# RAC_schematic_pcb.net
KiCad netlist of a schematic drawn in EasyEDA Pro
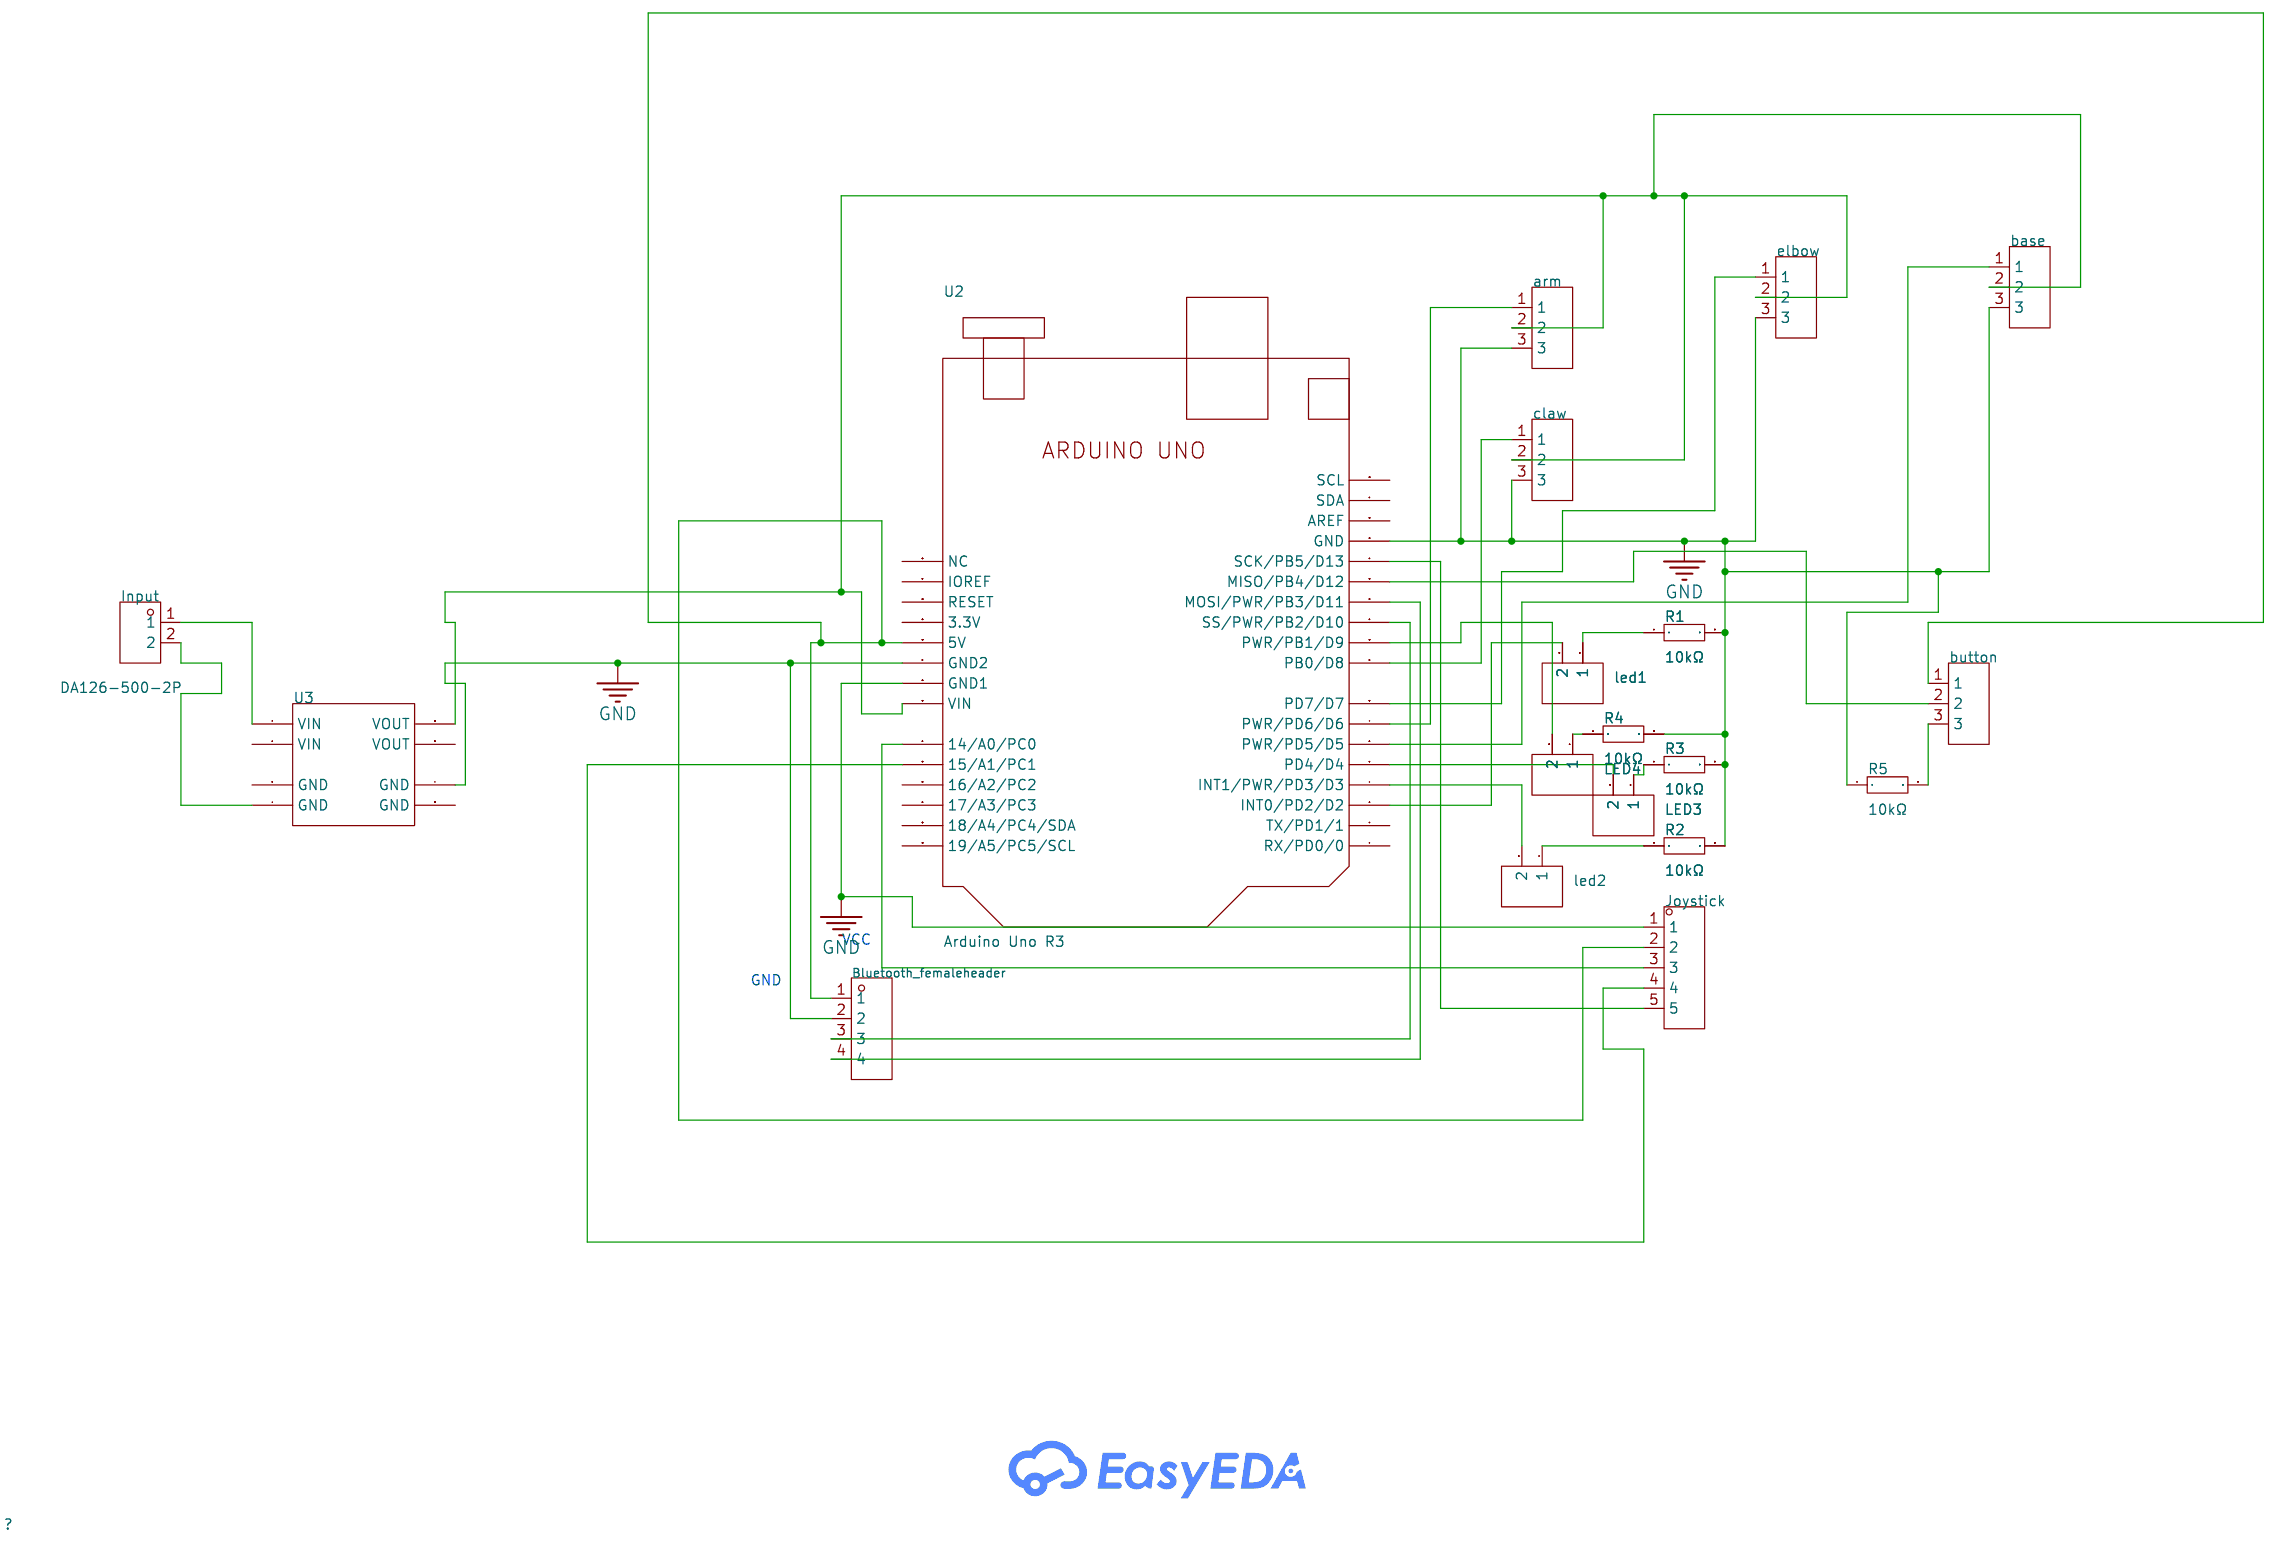
[diagram p0: schematic sheet]

(export (version "E")
  (design (tool "Eeschema 10.0.6"))
  (components
    (comp (ref "arm")
      (value "~")
      (footprint "easyedapro:HDR-TH_3P-P2.54-V-M")
      (libsource (lib "easyedapro") (part "PZ254V-11-03P_C2937625"))
    )
    (comp (ref "base")
      (value "~")
      (footprint "easyedapro:HDR-TH_3P-P2.54-V-M")
      (libsource (lib "easyedapro") (part "PZ254V-11-03P_C2937625"))
    )
    (comp (ref "Bluetooth_femaleheader")
      (value "~")
      (footprint "easyedapro:HDR-TH_4P-P2.54-V-F")
      (libsource (lib "easyedapro") (part "2.54-1*4P母"))
    )
    (comp (ref "button")
      (value "~")
      (footprint "easyedapro:HDR-TH_3P-P2.54-V-M")
      (libsource (lib "easyedapro") (part "PZ254V-11-03P_C2937625"))
    )
    (comp (ref "claw")
      (value "~")
      (footprint "easyedapro:HDR-TH_3P-P2.54-V-M")
      (libsource (lib "easyedapro") (part "PZ254V-11-03P_C2937625"))
    )
    (comp (ref "elbow")
      (value "~")
      (footprint "easyedapro:HDR-TH_3P-P2.54-V-M")
      (libsource (lib "easyedapro") (part "PZ254V-11-03P_C2937625"))
    )
    (comp (ref "Input")
      (value "DA126-500-2P")
      (footprint "easyedapro:CONN-TH_DA126-500-2P")
      (libsource (lib "easyedapro") (part "DA126-500-2P"))
    )
    (comp (ref "Joystick")
      (value "~")
      (footprint "easyedapro:HDR-TH_5P-P2.54-V-M")
      (libsource (lib "easyedapro") (part "MTP125-1105S1"))
    )
    (comp (ref "led1")
      (value "~")
      (footprint "easyedapro:HDR-TH_2P-P2.54-V-F")
      (fields (field (name "Manufacturer Part") "2.54-1*2P母") (field (name "Manufacturer") "BOOMELE(博穆精密)"))
      (libsource (lib "easyedapro") (part "Header-Female-2.54_1x2"))
    )
    (comp (ref "led2")
      (value "~")
      (footprint "easyedapro:HDR-TH_2P-P2.54-V-F")
      (fields (field (name "Manufacturer Part") "2.54-1*2P母") (field (name "Manufacturer") "BOOMELE(博穆精密)"))
      (libsource (lib "easyedapro") (part "Header-Female-2.54_1x2"))
    )
    (comp (ref "LED3")
      (value "~")
      (footprint "easyedapro:HDR-TH_2P-P2.54-V-F")
      (fields (field (name "Manufacturer Part") "2.54-1*2P母") (field (name "Manufacturer") "BOOMELE(博穆精密)"))
      (libsource (lib "easyedapro") (part "Header-Female-2.54_1x2"))
    )
    (comp (ref "LED4")
      (value "~")
      (footprint "easyedapro:HDR-TH_2P-P2.54-V-F")
      (fields (field (name "Manufacturer Part") "2.54-1*2P母") (field (name "Manufacturer") "BOOMELE(博穆精密)"))
      (libsource (lib "easyedapro") (part "Header-Female-2.54_1x2"))
    )
    (comp (ref "R1")
      (value "10kΩ")
      (footprint "easyedapro:R_AXIAL-0.4")
      (libsource (lib "easyedapro") (part "Res"))
    )
    (comp (ref "R2")
      (value "10kΩ")
      (footprint "easyedapro:R_AXIAL-0.4")
      (libsource (lib "easyedapro") (part "Res"))
    )
    (comp (ref "R3")
      (value "10kΩ")
      (footprint "easyedapro:R_AXIAL-0.4")
      (libsource (lib "easyedapro") (part "Res"))
    )
    (comp (ref "R4")
      (value "10kΩ")
      (footprint "easyedapro:R_AXIAL-0.4")
      (libsource (lib "easyedapro") (part "Res"))
    )
    (comp (ref "R5")
      (value "10kΩ")
      (footprint "easyedapro:R_AXIAL-0.4")
      (libsource (lib "easyedapro") (part "Res"))
    )
    (comp (ref "U2")
      (value "Arduino Uno R3")
      (footprint "easyedapro:UNO_R3;WO ARDUINO UNO")
      (fields (field (name "Manufacturer") "Arduino CC"))
      (libsource (lib "easyedapro") (part "Arduino Uno R3"))
    )
    (comp (ref "U3")
      (value "~")
      (footprint "easyedapro:Mini560")
      (libsource (lib "easyedapro") (part "Mini560"))
    )
  )
  (nets
    (net (code "1") (name "GND") (class "Default")
      (node (ref "Bluetooth_femaleheader") (pin "2") (pinfunction "2_2") (pintype "input"))
      (node (ref "Joystick") (pin "1") (pinfunction "1_1") (pintype "input"))
      (node (ref "R1") (pin "2") (pinfunction "2_2") (pintype "input"))
      (node (ref "R2") (pin "2") (pinfunction "2_2") (pintype "input"))
      (node (ref "R3") (pin "2") (pinfunction "2_2") (pintype "input"))
      (node (ref "R4") (pin "2") (pinfunction "2_2") (pintype "input"))
      (node (ref "R5") (pin "1") (pinfunction "1_1") (pintype "input"))
      (node (ref "U2") (pin "15") (pinfunction "GND_15") (pintype "unspecified"))
      (node (ref "U2") (pin "26") (pinfunction "GND1_26") (pintype "unspecified"))
      (node (ref "U2") (pin "27") (pinfunction "GND2_27") (pintype "unspecified"))
      (node (ref "U3") (pin "7") (pinfunction "GND_7") (pintype "input"))
      (node (ref "arm") (pin "3") (pinfunction "3_3") (pintype "unspecified"))
      (node (ref "base") (pin "3") (pinfunction "3_3") (pintype "unspecified"))
      (node (ref "claw") (pin "3") (pinfunction "3_3") (pintype "unspecified"))
      (node (ref "elbow") (pin "3") (pinfunction "3_3") (pintype "unspecified"))
    )
    (net (code "2") (name "Net-(Input-Pad1)") (class "Default")
      (node (ref "Input") (pin "1") (pinfunction "1_1") (pintype "input"))
      (node (ref "U3") (pin "1") (pinfunction "VIN_1") (pintype "input"))
    )
    (net (code "3") (name "Net-(Input-Pad2)") (class "Default")
      (node (ref "Input") (pin "2") (pinfunction "2_2") (pintype "input"))
      (node (ref "U3") (pin "4") (pinfunction "GND_4") (pintype "input"))
    )
    (net (code "4") (name "Net-(LED3-Pad1)") (class "Default")
      (node (ref "LED3") (pin "1") (pinfunction "1_1") (pintype "input"))
      (node (ref "R3") (pin "1") (pinfunction "1_1") (pintype "input"))
    )
    (net (code "5") (name "Net-(LED4-Pad1)") (class "Default")
      (node (ref "LED4") (pin "1") (pinfunction "1_1") (pintype "input"))
      (node (ref "R4") (pin "1") (pinfunction "1_1") (pintype "input"))
    )
    (net (code "6") (name "Net-(R1-Pad1)") (class "Default")
      (node (ref "R1") (pin "1") (pinfunction "1_1") (pintype "input"))
      (node (ref "led1") (pin "1") (pinfunction "1_1") (pintype "input"))
    )
    (net (code "7") (name "Net-(R2-Pad1)") (class "Default")
      (node (ref "R2") (pin "1") (pinfunction "1_1") (pintype "input"))
      (node (ref "led2") (pin "1") (pinfunction "1_1") (pintype "input"))
    )
    (net (code "8") (name "Net-(R5-Pad2)") (class "Default")
      (node (ref "R5") (pin "2") (pinfunction "2_2") (pintype "input"))
      (node (ref "button") (pin "3") (pinfunction "3_3") (pintype "unspecified"))
    )
    (net (code "9") (name "Net-(U2-5V)") (class "Default")
      (node (ref "Bluetooth_femaleheader") (pin "1") (pinfunction "1_1") (pintype "input"))
      (node (ref "Joystick") (pin "2") (pinfunction "2_2") (pintype "input"))
      (node (ref "U2") (pin "28") (pinfunction "5V_28") (pintype "unspecified"))
      (node (ref "button") (pin "1") (pinfunction "1_1") (pintype "unspecified"))
    )
    (net (code "10") (name "Net-(U2-14{slash}A0{slash}PC0)") (class "Default")
      (node (ref "Joystick") (pin "3") (pinfunction "3_3") (pintype "input"))
      (node (ref "U2") (pin "24") (pinfunction "14/A0/PC0_24") (pintype "bidirectional"))
    )
    (net (code "11") (name "Net-(U2-15{slash}A1{slash}PC1)") (class "Default")
      (node (ref "Joystick") (pin "4") (pinfunction "4_4") (pintype "input"))
      (node (ref "U2") (pin "23") (pinfunction "15/A1/PC1_23") (pintype "bidirectional"))
    )
    (net (code "12") (name "Net-(U2-INT0{slash}PD2{slash}D2)") (class "Default")
      (node (ref "U2") (pin "3") (pinfunction "INT0/PD2/D2_3") (pintype "bidirectional"))
      (node (ref "led1") (pin "2") (pinfunction "2_2") (pintype "input"))
    )
    (net (code "13") (name "Net-(U2-INT1{slash}PWR{slash}PD3{slash}D3)") (class "Default")
      (node (ref "U2") (pin "4") (pinfunction "INT1/PWR/PD3/D3_4") (pintype "bidirectional"))
      (node (ref "led2") (pin "2") (pinfunction "2_2") (pintype "input"))
    )
    (net (code "14") (name "Net-(U2-MISO{slash}PB4{slash}D12)") (class "Default")
      (node (ref "U2") (pin "13") (pinfunction "MISO/PB4/D12_13") (pintype "bidirectional"))
      (node (ref "button") (pin "2") (pinfunction "2_2") (pintype "unspecified"))
    )
    (net (code "15") (name "Net-(U2-MOSI{slash}PWR{slash}PB3{slash}D11)") (class "Default")
      (node (ref "Bluetooth_femaleheader") (pin "4") (pinfunction "4_4") (pintype "input"))
      (node (ref "U2") (pin "12") (pinfunction "MOSI/PWR/PB3/D11_12") (pintype "bidirectional"))
    )
    (net (code "16") (name "Net-(U2-PB0{slash}D8)") (class "Default")
      (node (ref "U2") (pin "9") (pinfunction "PB0/D8_9") (pintype "bidirectional"))
      (node (ref "claw") (pin "1") (pinfunction "1_1") (pintype "unspecified"))
    )
    (net (code "17") (name "Net-(U2-PD4{slash}D4)") (class "Default")
      (node (ref "LED3") (pin "2") (pinfunction "2_2") (pintype "input"))
      (node (ref "U2") (pin "5") (pinfunction "PD4/D4_5") (pintype "bidirectional"))
    )
    (net (code "18") (name "Net-(U2-PD7{slash}D7)") (class "Default")
      (node (ref "U2") (pin "8") (pinfunction "PD7/D7_8") (pintype "bidirectional"))
      (node (ref "elbow") (pin "1") (pinfunction "1_1") (pintype "unspecified"))
    )
    (net (code "19") (name "Net-(U2-PWR{slash}PB1{slash}D9)") (class "Default")
      (node (ref "LED4") (pin "2") (pinfunction "2_2") (pintype "input"))
      (node (ref "U2") (pin "10") (pinfunction "PWR/PB1/D9_10") (pintype "bidirectional"))
    )
    (net (code "20") (name "Net-(U2-PWR{slash}PD5{slash}D5)") (class "Default")
      (node (ref "U2") (pin "6") (pinfunction "PWR/PD5/D5_6") (pintype "bidirectional"))
      (node (ref "base") (pin "1") (pinfunction "1_1") (pintype "unspecified"))
    )
    (net (code "21") (name "Net-(U2-PWR{slash}PD6{slash}D6)") (class "Default")
      (node (ref "U2") (pin "7") (pinfunction "PWR/PD6/D6_7") (pintype "bidirectional"))
      (node (ref "arm") (pin "1") (pinfunction "1_1") (pintype "unspecified"))
    )
    (net (code "22") (name "Net-(U2-SCK{slash}PB5{slash}D13)") (class "Default")
      (node (ref "Joystick") (pin "5") (pinfunction "5_5") (pintype "input"))
      (node (ref "U2") (pin "14") (pinfunction "SCK/PB5/D13_14") (pintype "bidirectional"))
    )
    (net (code "23") (name "Net-(U2-SS{slash}PWR{slash}PB2{slash}D10)") (class "Default")
      (node (ref "Bluetooth_femaleheader") (pin "3") (pinfunction "3_3") (pintype "input"))
      (node (ref "U2") (pin "11") (pinfunction "SS/PWR/PB2/D10_11") (pintype "bidirectional"))
    )
    (net (code "24") (name "Net-(U2-VIN)") (class "Default")
      (node (ref "U2") (pin "25") (pinfunction "VIN_25") (pintype "unspecified"))
      (node (ref "U3") (pin "5") (pinfunction "VOUT_5") (pintype "input"))
      (node (ref "arm") (pin "2") (pinfunction "2_2") (pintype "unspecified"))
      (node (ref "base") (pin "2") (pinfunction "2_2") (pintype "unspecified"))
      (node (ref "claw") (pin "2") (pinfunction "2_2") (pintype "unspecified"))
      (node (ref "elbow") (pin "2") (pinfunction "2_2") (pintype "unspecified"))
    )
    (net (code "25") (name "unconnected-(U2-3.3V-Pad29)") (class "Default")
      (node (ref "U2") (pin "29") (pinfunction "3.3V_29") (pintype "unspecified"))
    )
    (net (code "26") (name "unconnected-(U2-16{slash}A2{slash}PC2-Pad22)") (class "Default")
      (node (ref "U2") (pin "22") (pinfunction "16/A2/PC2_22") (pintype "bidirectional"))
    )
    (net (code "27") (name "unconnected-(U2-17{slash}A3{slash}PC3-Pad21)") (class "Default")
      (node (ref "U2") (pin "21") (pinfunction "17/A3/PC3_21") (pintype "bidirectional"))
    )
    (net (code "28") (name "unconnected-(U2-18{slash}A4{slash}PC4{slash}SDA-Pad20)") (class "Default")
      (node (ref "U2") (pin "20") (pinfunction "18/A4/PC4/SDA_20") (pintype "bidirectional"))
    )
    (net (code "29") (name "unconnected-(U2-19{slash}A5{slash}PC5{slash}SCL-Pad19)") (class "Default")
      (node (ref "U2") (pin "19") (pinfunction "19/A5/PC5/SCL_19") (pintype "bidirectional"))
    )
    (net (code "30") (name "unconnected-(U2-AREF-Pad16)") (class "Default")
      (node (ref "U2") (pin "16") (pinfunction "AREF_16") (pintype "unspecified"))
    )
    (net (code "31") (name "unconnected-(U2-IOREF-Pad31)") (class "Default")
      (node (ref "U2") (pin "31") (pinfunction "IOREF_31") (pintype "unspecified"))
    )
    (net (code "32") (name "unconnected-(U2-NC-Pad32)") (class "Default")
      (node (ref "U2") (pin "32") (pinfunction "NC_32") (pintype "unspecified"))
    )
    (net (code "33") (name "unconnected-(U2-RESET-Pad30)") (class "Default")
      (node (ref "U2") (pin "30") (pinfunction "RESET_30") (pintype "unspecified"))
    )
    (net (code "34") (name "unconnected-(U2-RX{slash}PD0{slash}0-Pad1)") (class "Default")
      (node (ref "U2") (pin "1") (pinfunction "RX/PD0/0_1") (pintype "unspecified"))
    )
    (net (code "35") (name "unconnected-(U2-SCL-Pad18)") (class "Default")
      (node (ref "U2") (pin "18") (pinfunction "SCL_18") (pintype "unspecified"))
    )
    (net (code "36") (name "unconnected-(U2-SDA-Pad17)") (class "Default")
      (node (ref "U2") (pin "17") (pinfunction "SDA_17") (pintype "unspecified"))
    )
    (net (code "37") (name "unconnected-(U2-TX{slash}PD1{slash}1-Pad2)") (class "Default")
      (node (ref "U2") (pin "2") (pinfunction "TX/PD1/1_2") (pintype "unspecified"))
    )
    (net (code "38") (name "unconnected-(U3-GND-Pad3)") (class "Default")
      (node (ref "U3") (pin "3") (pinfunction "GND_3") (pintype "input"))
    )
    (net (code "39") (name "unconnected-(U3-GND-Pad8)") (class "Default")
      (node (ref "U3") (pin "8") (pinfunction "GND_8") (pintype "input"))
    )
    (net (code "40") (name "unconnected-(U3-VIN-Pad2)") (class "Default")
      (node (ref "U3") (pin "2") (pinfunction "VIN_2") (pintype "input"))
    )
    (net (code "41") (name "unconnected-(U3-VOUT-Pad6)") (class "Default")
      (node (ref "U3") (pin "6") (pinfunction "VOUT_6") (pintype "input"))
    )
  )
)
